# Sheet1.net
KiCad netlist of a schematic drawn in Altium Designer
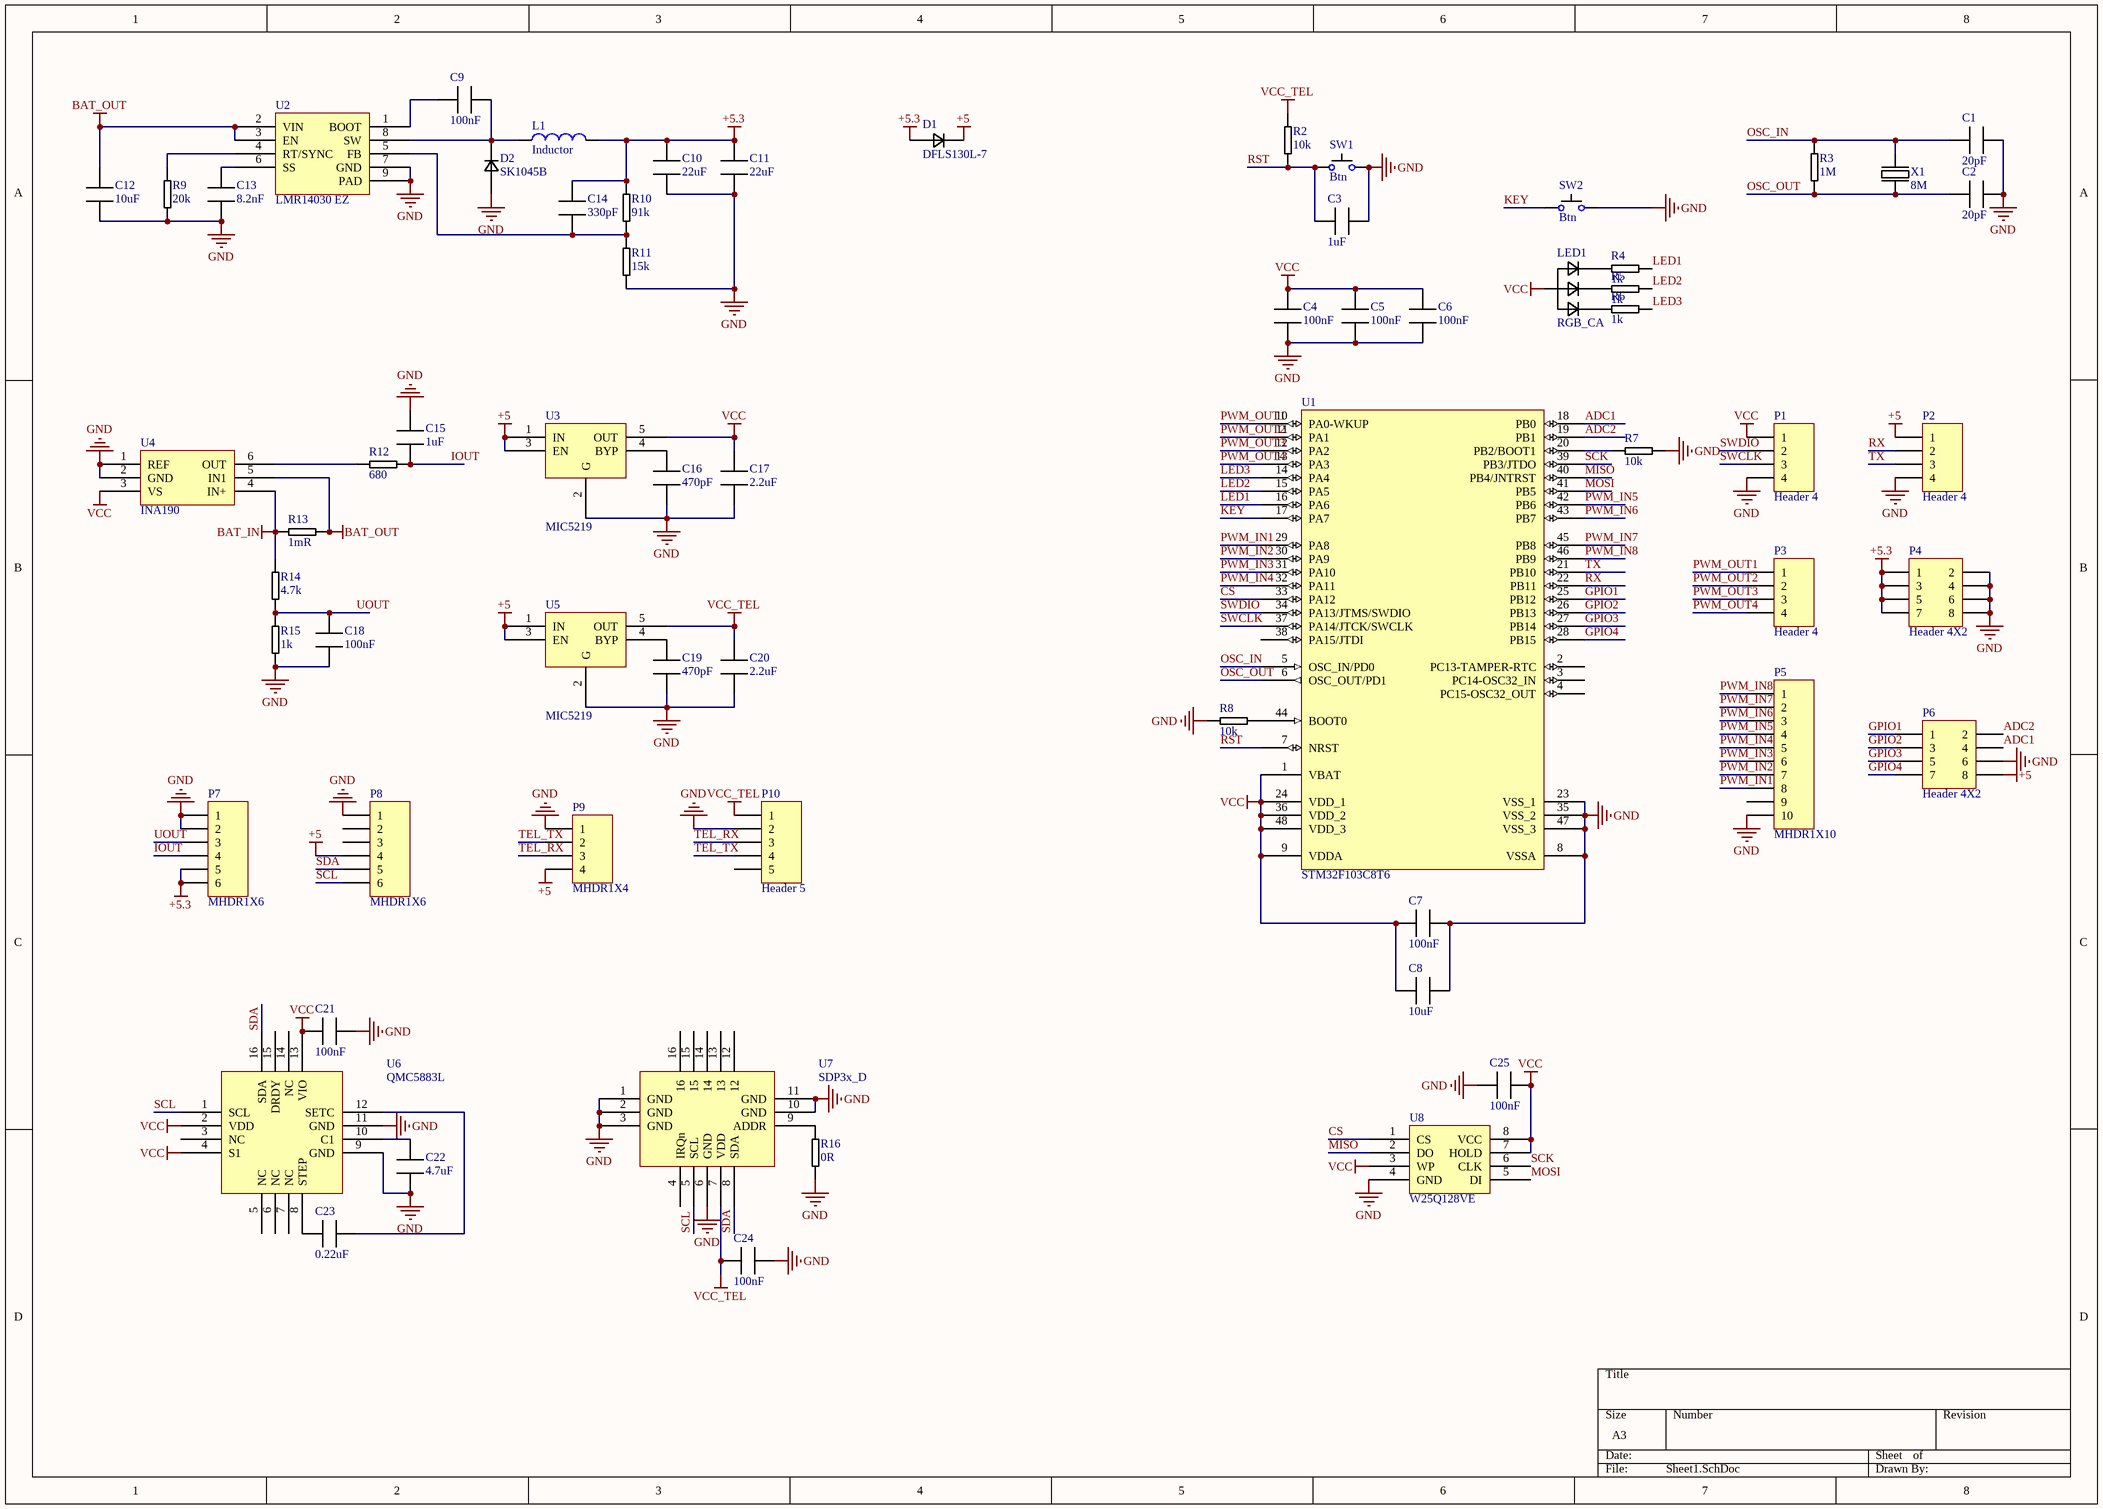
[diagram p0: Sheet1.SchDoc]

(export (version "E")
  (design (tool "Eeschema 10.0.6"))
  (components
    (comp (ref "C1") (value "20pF") (footprint "0603") (libsource (lib "LibCfrpg") (part "Cap")))
    (comp (ref "C2") (value "20pF") (footprint "0603") (libsource (lib "LibCfrpg") (part "Cap")))
    (comp (ref "C3") (value "1uF") (footprint "0603") (libsource (lib "LibCfrpg") (part "Cap")))
    (comp (ref "C4") (value "100nF") (footprint "0603") (libsource (lib "LibCfrpg") (part "Cap")))
    (comp (ref "C5") (value "100nF") (footprint "0603") (libsource (lib "LibCfrpg") (part "Cap")))
    (comp (ref "C6") (value "100nF") (footprint "0603") (libsource (lib "LibCfrpg") (part "Cap")))
    (comp (ref "C7") (value "100nF") (footprint "0603") (libsource (lib "LibCfrpg") (part "Cap")))
    (comp (ref "C8") (value "10uF") (footprint "0603") (libsource (lib "LibCfrpg") (part "Cap")))
    (comp (ref "C9") (value "100nF") (footprint "0603") (libsource (lib "LibCfrpg") (part "Cap")))
    (comp (ref "C10") (value "22uF") (footprint "0603") (libsource (lib "LibCfrpg") (part "Cap")))
    (comp (ref "C11") (value "22uF") (footprint "0603") (libsource (lib "LibCfrpg") (part "Cap")))
    (comp (ref "C12") (value "10uF") (footprint "1210") (libsource (lib "LibCfrpg") (part "Cap")))
    (comp (ref "C13") (value "8.2nF") (footprint "0603") (libsource (lib "LibCfrpg") (part "Cap")))
    (comp (ref "C14") (value "330pF") (footprint "0603") (libsource (lib "LibCfrpg") (part "Cap")))
    (comp (ref "C15") (value "1uF") (footprint "0603") (libsource (lib "LibCfrpg") (part "Cap")))
    (comp (ref "C16") (value "470pF") (footprint "0603") (libsource (lib "LibCfrpg") (part "Cap")))
    (comp (ref "C17") (value "2.2uF") (footprint "0603") (libsource (lib "LibCfrpg") (part "Cap")))
    (comp (ref "C18") (value "100nF") (footprint "0603") (libsource (lib "LibCfrpg") (part "Cap")))
    (comp (ref "C19") (value "470pF") (footprint "0603") (libsource (lib "LibCfrpg") (part "Cap")))
    (comp (ref "C20") (value "2.2uF") (footprint "0603") (libsource (lib "LibCfrpg") (part "Cap")))
    (comp (ref "C21") (value "100nF") (footprint "0603") (libsource (lib "LibCfrpg") (part "Cap")))
    (comp (ref "C22") (value "4.7uF") (footprint "0603") (libsource (lib "LibCfrpg") (part "Cap")))
    (comp (ref "C23") (value "0.22uF") (footprint "0603") (libsource (lib "LibCfrpg") (part "Cap")))
    (comp (ref "C24") (value "100nF") (footprint "0603") (libsource (lib "LibCfrpg") (part "Cap")))
    (comp (ref "C25") (value "100nF") (footprint "0603") (libsource (lib "LibCfrpg") (part "Cap")))
    (comp (ref "D1")
      (value "DFLS130L-7")
      (footprint "PowerDI123")
      (libsource (lib "LibCfrpg") (part "Diode"))
    )
    (comp (ref "D2")
      (value "SK1045B")
      (footprint "SMB (DO-214AA)")
      (libsource (lib "LibCfrpg") (part "Diode"))
    )
    (comp (ref "L1") (value "Inductor") (footprint "Ind1040") (libsource (lib "LibCfrpg") (part "Inductor")))
    (comp (ref "LED1") (value "RGB_CA") (footprint "RGB1.6*1.6") (libsource (lib "LibCfrpg") (part "RGB_CA")))
    (comp (ref "P1")
      (value "Header 4")
      (footprint "HDR1X4")
      (description "Header, 4-Pin")
      (fields (field (name "PUBLISHER") "Altium Limited"))
      (libsource (lib "Miscellaneous Connectors") (part "Header 4"))
    )
    (comp (ref "P2")
      (value "Header 4")
      (footprint "HDR1X4")
      (description "Header, 4-Pin")
      (fields (field (name "PUBLISHER") "Altium Limited"))
      (libsource (lib "Miscellaneous Connectors") (part "Header 4"))
    )
    (comp (ref "P3")
      (value "Header 4")
      (footprint "HDR1X4")
      (description "Header, 4-Pin")
      (fields (field (name "PUBLISHER") "Altium Limited"))
      (libsource (lib "Miscellaneous Connectors") (part "Header 4"))
    )
    (comp (ref "P4")
      (value "Header 4X2")
      (footprint "HDR2X4")
      (description "Header, 4-Pin, Dual row")
      (fields (field (name "PUBLISHER") "Altium Limited"))
      (libsource (lib "Miscellaneous Connectors") (part "Header 4X2"))
    )
    (comp (ref "P5")
      (value "MHDR1X10")
      (footprint "MHDR1X10")
      (description "Header, 10-Pin")
      (fields (field (name "PUBLISHER") "Altium Limited"))
      (libsource (lib "Miscellaneous Connectors") (part "MHDR1X10"))
    )
    (comp (ref "P6")
      (value "Header 4X2")
      (footprint "HDR2X4")
      (description "Header, 4-Pin, Dual row")
      (fields (field (name "PUBLISHER") "Altium Limited"))
      (libsource (lib "Miscellaneous Connectors") (part "Header 4X2"))
    )
    (comp (ref "P7")
      (value "MHDR1X6")
      (footprint "MHDR1X6")
      (description "Header, 6-Pin")
      (fields (field (name "PUBLISHER") "Altium Limited"))
      (libsource (lib "Miscellaneous Connectors") (part "MHDR1X6"))
    )
    (comp (ref "P8")
      (value "MHDR1X6")
      (footprint "MHDR1X6")
      (description "Header, 6-Pin")
      (fields (field (name "PUBLISHER") "Altium Limited"))
      (libsource (lib "Miscellaneous Connectors") (part "MHDR1X6"))
    )
    (comp (ref "P9")
      (value "MHDR1X4")
      (footprint "MHDR1X4")
      (description "Header, 4-Pin")
      (fields (field (name "PUBLISHER") "Altium Limited"))
      (libsource (lib "Miscellaneous Connectors") (part "MHDR1X4"))
    )
    (comp (ref "P10")
      (value "Header 5")
      (footprint "HDR1X5")
      (description "Header, 5-Pin")
      (fields (field (name "PUBLISHER") "Altium Limited"))
      (libsource (lib "Miscellaneous Connectors") (part "Header 5"))
    )
    (comp (ref "R2") (value "10k") (footprint "0603") (libsource (lib "LibCfrpg") (part "Res")))
    (comp (ref "R3") (value "1M") (footprint "0603") (libsource (lib "LibCfrpg") (part "Res")))
    (comp (ref "R4") (value "1k") (footprint "0603") (libsource (lib "LibCfrpg") (part "Res")))
    (comp (ref "R5") (value "1k") (footprint "0603") (libsource (lib "LibCfrpg") (part "Res")))
    (comp (ref "R6") (value "1k") (footprint "0603") (libsource (lib "LibCfrpg") (part "Res")))
    (comp (ref "R7") (value "10k") (footprint "0603") (libsource (lib "LibCfrpg") (part "Res")))
    (comp (ref "R8") (value "10k") (footprint "0603") (libsource (lib "LibCfrpg") (part "Res")))
    (comp (ref "R9") (value "20k") (footprint "0603") (libsource (lib "LibCfrpg") (part "Res")))
    (comp (ref "R10") (value "91k") (footprint "0603") (libsource (lib "LibCfrpg") (part "Res")))
    (comp (ref "R11") (value "15k") (footprint "0603") (libsource (lib "LibCfrpg") (part "Res")))
    (comp (ref "R12") (value "680") (footprint "0603") (libsource (lib "LibCfrpg") (part "Res")))
    (comp (ref "R13") (value "1mR") (footprint "2512") (libsource (lib "LibCfrpg") (part "Res")))
    (comp (ref "R14") (value "4.7k") (footprint "0603") (libsource (lib "LibCfrpg") (part "Res")))
    (comp (ref "R15") (value "1k") (footprint "0603") (libsource (lib "LibCfrpg") (part "Res")))
    (comp (ref "R16") (value "0R") (footprint "0603") (libsource (lib "LibCfrpg") (part "Res")))
    (comp (ref "SW1") (value "Btn") (footprint "BTN_B3U_B") (libsource (lib "LibCfrpg") (part "Btn")))
    (comp (ref "SW2") (value "Btn") (footprint "BTN_B3U_B") (libsource (lib "LibCfrpg") (part "Btn")))
    (comp (ref "U1")
      (value "STM32F103C8T6")
      (footprint "LQFP48_N")
      (description "STM32 ARM-based 32-bit MCU with 64 Kbytes Flash, 48-pin LQFP, Industrial Temperature")
      (fields (field (name "PUBLISHER") "Altium Limited"))
      (libsource (lib "ST Microcontroller 32-Bit STM32") (part "STM32F103C8T6"))
    )
    (comp (ref "U2")
      (value "LMR14030 EZ")
      (footprint "SOP8-Pad")
      (libsource (lib "LibCfrpg") (part "LMR14030 EZ"))
    )
    (comp (ref "U3") (value "MIC5219") (footprint "SOT23-5") (libsource (lib "LibCfrpg") (part "MIC5219")))
    (comp (ref "U4") (value "INA190") (footprint "SC70") (libsource (lib "LibCfrpg") (part "INA190")))
    (comp (ref "U5") (value "MIC5219") (footprint "SOT23-5") (libsource (lib "LibCfrpg") (part "MIC5219")))
    (comp (ref "U6") (value "QMC5883L") (footprint "QMC5883") (libsource (lib "LibCfrpg") (part "QMC5883L")))
    (comp (ref "U7") (value "SDP3x_D") (footprint "SDP3x") (libsource (lib "LibCfrpg") (part "SDP3x_D")))
    (comp (ref "U8")
      (value "W25Q128VE")
      (footprint "WSON8-8x6mm")
      (libsource (lib "LibCfrpg") (part "W25QxxxVE/A"))
    )
    (comp (ref "X1") (value "8M") (footprint "XTAL-3225-4") (libsource (lib "LibCfrpg") (part "XTAL")))
  )
  (nets
    (net (code "1") (name "+5") (class "Default")
      (node (ref "D1") (pin "2") (pintype "passive"))
      (node (ref "P2") (pin "1") (pinfunction "1_1") (pintype "passive"))
      (node (ref "P6") (pin "8") (pinfunction "8_8") (pintype "passive"))
      (node (ref "P8") (pin "4") (pinfunction "4_4") (pintype "passive"))
      (node (ref "P9") (pin "4") (pinfunction "4_4") (pintype "passive"))
      (node (ref "U3") (pin "1") (pinfunction "IN_1") (pintype "passive"))
      (node (ref "U3") (pin "3") (pinfunction "EN_3") (pintype "passive"))
      (node (ref "U5") (pin "1") (pinfunction "IN_1") (pintype "passive"))
      (node (ref "U5") (pin "3") (pinfunction "EN_3") (pintype "passive"))
    )
    (net (code "2") (name "+5.3") (class "Default")
      (node (ref "C10") (pin "2") (pintype "passive"))
      (node (ref "C11") (pin "2") (pintype "passive"))
      (node (ref "C14") (pin "2") (pintype "passive"))
      (node (ref "D1") (pin "1") (pintype "passive"))
      (node (ref "L1") (pin "2") (pinfunction "2_2") (pintype "passive"))
      (node (ref "P4") (pin "1") (pinfunction "1_1") (pintype "passive"))
      (node (ref "P4") (pin "3") (pinfunction "3_3") (pintype "passive"))
      (node (ref "P4") (pin "5") (pinfunction "5_5") (pintype "passive"))
      (node (ref "P4") (pin "7") (pinfunction "7_7") (pintype "passive"))
      (node (ref "P7") (pin "5") (pinfunction "5_5") (pintype "passive"))
      (node (ref "P7") (pin "6") (pinfunction "6_6") (pintype "passive"))
      (node (ref "R10") (pin "2") (pintype "passive"))
    )
    (net (code "3") (name "/ADC1") (class "Default")
      (node (ref "P6") (pin "4") (pinfunction "4_4") (pintype "passive"))
      (node (ref "U1") (pin "18") (pinfunction "PB0_18") (pintype "bidirectional"))
    )
    (net (code "4") (name "/ADC2") (class "Default")
      (node (ref "P6") (pin "2") (pinfunction "2_2") (pintype "passive"))
      (node (ref "U1") (pin "19") (pinfunction "PB1_19") (pintype "bidirectional"))
    )
    (net (code "5") (name "/CS") (class "Default")
      (node (ref "U1") (pin "33") (pinfunction "PA12_33") (pintype "bidirectional"))
      (node (ref "U8") (pin "1") (pinfunction "CS_1") (pintype "passive"))
    )
    (net (code "6") (name "/GPIO1") (class "Default")
      (node (ref "P6") (pin "1") (pinfunction "1_1") (pintype "passive"))
      (node (ref "U1") (pin "25") (pinfunction "PB12_25") (pintype "bidirectional"))
    )
    (net (code "7") (name "/GPIO2") (class "Default")
      (node (ref "P6") (pin "3") (pinfunction "3_3") (pintype "passive"))
      (node (ref "U1") (pin "26") (pinfunction "PB13_26") (pintype "bidirectional"))
    )
    (net (code "8") (name "/GPIO3") (class "Default")
      (node (ref "P6") (pin "5") (pinfunction "5_5") (pintype "passive"))
      (node (ref "U1") (pin "27") (pinfunction "PB14_27") (pintype "bidirectional"))
    )
    (net (code "9") (name "/GPIO4") (class "Default")
      (node (ref "P6") (pin "7") (pinfunction "7_7") (pintype "passive"))
      (node (ref "U1") (pin "28") (pinfunction "PB15_28") (pintype "bidirectional"))
    )
    (net (code "10") (name "/IOUT") (class "Default")
      (node (ref "C15") (pin "1") (pintype "passive"))
      (node (ref "P7") (pin "4") (pinfunction "4_4") (pintype "passive"))
      (node (ref "R12") (pin "2") (pintype "passive"))
    )
    (net (code "11") (name "/KEY") (class "Default")
      (node (ref "SW2") (pin "1") (pintype "passive"))
      (node (ref "U1") (pin "17") (pinfunction "PA7_17") (pintype "bidirectional"))
    )
    (net (code "12") (name "/LED1") (class "Default")
      (node (ref "R4") (pin "2") (pintype "passive"))
      (node (ref "U1") (pin "16") (pinfunction "PA6_16") (pintype "bidirectional"))
    )
    (net (code "13") (name "/LED2") (class "Default")
      (node (ref "R5") (pin "2") (pintype "passive"))
      (node (ref "U1") (pin "15") (pinfunction "PA5_15") (pintype "bidirectional"))
    )
    (net (code "14") (name "/LED3") (class "Default")
      (node (ref "R6") (pin "2") (pintype "passive"))
      (node (ref "U1") (pin "14") (pinfunction "PA4_14") (pintype "bidirectional"))
    )
    (net (code "15") (name "/MISO") (class "Default")
      (node (ref "U1") (pin "40") (pinfunction "PB4/JNTRST_40") (pintype "bidirectional"))
      (node (ref "U8") (pin "2") (pinfunction "DO_2") (pintype "passive"))
    )
    (net (code "16") (name "/MOSI") (class "Default")
      (node (ref "U1") (pin "41") (pinfunction "PB5_41") (pintype "bidirectional"))
      (node (ref "U8") (pin "5") (pinfunction "DI_5") (pintype "passive"))
    )
    (net (code "17") (name "/OSC_IN") (class "Default")
      (node (ref "C1") (pin "1") (pintype "passive"))
      (node (ref "R3") (pin "2") (pintype "passive"))
      (node (ref "U1") (pin "5") (pinfunction "OSC_IN/PD0_5") (pintype "input"))
      (node (ref "X1") (pin "2") (pintype "passive"))
    )
    (net (code "18") (name "/OSC_OUT") (class "Default")
      (node (ref "C2") (pin "1") (pintype "passive"))
      (node (ref "R3") (pin "1") (pintype "passive"))
      (node (ref "U1") (pin "6") (pinfunction "OSC_OUT/PD1_6") (pintype "output"))
      (node (ref "X1") (pin "1") (pintype "passive"))
    )
    (net (code "19") (name "/PWM_IN1") (class "Default")
      (node (ref "P5") (pin "8") (pinfunction "8_8") (pintype "passive"))
      (node (ref "U1") (pin "29") (pinfunction "PA8_29") (pintype "bidirectional"))
    )
    (net (code "20") (name "/PWM_IN2") (class "Default")
      (node (ref "P5") (pin "7") (pinfunction "7_7") (pintype "passive"))
      (node (ref "U1") (pin "30") (pinfunction "PA9_30") (pintype "bidirectional"))
    )
    (net (code "21") (name "/PWM_IN3") (class "Default")
      (node (ref "P5") (pin "6") (pinfunction "6_6") (pintype "passive"))
      (node (ref "U1") (pin "31") (pinfunction "PA10_31") (pintype "bidirectional"))
    )
    (net (code "22") (name "/PWM_IN4") (class "Default")
      (node (ref "P5") (pin "5") (pinfunction "5_5") (pintype "passive"))
      (node (ref "U1") (pin "32") (pinfunction "PA11_32") (pintype "bidirectional"))
    )
    (net (code "23") (name "/PWM_IN5") (class "Default")
      (node (ref "P5") (pin "4") (pinfunction "4_4") (pintype "passive"))
      (node (ref "U1") (pin "42") (pinfunction "PB6_42") (pintype "bidirectional"))
    )
    (net (code "24") (name "/PWM_IN6") (class "Default")
      (node (ref "P5") (pin "3") (pinfunction "3_3") (pintype "passive"))
      (node (ref "U1") (pin "43") (pinfunction "PB7_43") (pintype "bidirectional"))
    )
    (net (code "25") (name "/PWM_IN7") (class "Default")
      (node (ref "P5") (pin "2") (pinfunction "2_2") (pintype "passive"))
      (node (ref "U1") (pin "45") (pinfunction "PB8_45") (pintype "bidirectional"))
    )
    (net (code "26") (name "/PWM_IN8") (class "Default")
      (node (ref "P5") (pin "1") (pinfunction "1_1") (pintype "passive"))
      (node (ref "U1") (pin "46") (pinfunction "PB9_46") (pintype "bidirectional"))
    )
    (net (code "27") (name "/PWM_OUT1") (class "Default")
      (node (ref "P3") (pin "1") (pinfunction "1_1") (pintype "passive"))
      (node (ref "U1") (pin "10") (pinfunction "PA0-WKUP_10") (pintype "bidirectional"))
    )
    (net (code "28") (name "/PWM_OUT2") (class "Default")
      (node (ref "P3") (pin "2") (pinfunction "2_2") (pintype "passive"))
      (node (ref "U1") (pin "11") (pinfunction "PA1_11") (pintype "bidirectional"))
    )
    (net (code "29") (name "/PWM_OUT3") (class "Default")
      (node (ref "P3") (pin "3") (pinfunction "3_3") (pintype "passive"))
      (node (ref "U1") (pin "12") (pinfunction "PA2_12") (pintype "bidirectional"))
    )
    (net (code "30") (name "/PWM_OUT4") (class "Default")
      (node (ref "P3") (pin "4") (pinfunction "4_4") (pintype "passive"))
      (node (ref "U1") (pin "13") (pinfunction "PA3_13") (pintype "bidirectional"))
    )
    (net (code "31") (name "/RST") (class "Default")
      (node (ref "C3") (pin "1") (pintype "passive"))
      (node (ref "R2") (pin "1") (pintype "passive"))
      (node (ref "SW1") (pin "1") (pintype "passive"))
      (node (ref "U1") (pin "7") (pinfunction "NRST_7") (pintype "bidirectional"))
    )
    (net (code "32") (name "/RX") (class "Default")
      (node (ref "P2") (pin "2") (pinfunction "2_2") (pintype "passive"))
      (node (ref "U1") (pin "22") (pinfunction "PB11_22") (pintype "bidirectional"))
    )
    (net (code "33") (name "/SCK") (class "Default")
      (node (ref "U1") (pin "39") (pinfunction "PB3/JTDO_39") (pintype "bidirectional"))
      (node (ref "U8") (pin "6") (pinfunction "CLK_6") (pintype "passive"))
    )
    (net (code "34") (name "/SCL") (class "Default")
      (node (ref "P8") (pin "6") (pinfunction "6_6") (pintype "passive"))
      (node (ref "U6") (pin "1") (pinfunction "SCL_1") (pintype "passive"))
      (node (ref "U7") (pin "5") (pinfunction "SCL_5") (pintype "passive"))
    )
    (net (code "35") (name "/SDA") (class "Default")
      (node (ref "P8") (pin "5") (pinfunction "5_5") (pintype "passive"))
      (node (ref "U6") (pin "16") (pinfunction "SDA_16") (pintype "passive"))
      (node (ref "U7") (pin "8") (pinfunction "SDA_8") (pintype "passive"))
    )
    (net (code "36") (name "/SWCLK") (class "Default")
      (node (ref "P1") (pin "3") (pinfunction "3_3") (pintype "passive"))
      (node (ref "U1") (pin "37") (pinfunction "PA14/JTCK/SWCLK_37") (pintype "bidirectional"))
    )
    (net (code "37") (name "/SWDIO") (class "Default")
      (node (ref "P1") (pin "2") (pinfunction "2_2") (pintype "passive"))
      (node (ref "U1") (pin "34") (pinfunction "PA13/JTMS/SWDIO_34") (pintype "bidirectional"))
    )
    (net (code "38") (name "/TEL_RX") (class "Default")
      (node (ref "P10") (pin "3") (pinfunction "3_3") (pintype "passive"))
      (node (ref "P9") (pin "3") (pinfunction "3_3") (pintype "passive"))
    )
    (net (code "39") (name "/TEL_TX") (class "Default")
      (node (ref "P10") (pin "4") (pinfunction "4_4") (pintype "passive"))
      (node (ref "P9") (pin "2") (pinfunction "2_2") (pintype "passive"))
    )
    (net (code "40") (name "/TX") (class "Default")
      (node (ref "P2") (pin "3") (pinfunction "3_3") (pintype "passive"))
      (node (ref "U1") (pin "21") (pinfunction "PB10_21") (pintype "bidirectional"))
    )
    (net (code "41") (name "/UOUT") (class "Default")
      (node (ref "C18") (pin "2") (pintype "passive"))
      (node (ref "P7") (pin "3") (pinfunction "3_3") (pintype "passive"))
      (node (ref "R14") (pin "1") (pintype "passive"))
      (node (ref "R15") (pin "2") (pintype "passive"))
    )
    (net (code "42") (name "BAT_IN") (class "Default")
      (node (ref "R13") (pin "1") (pintype "passive"))
      (node (ref "R14") (pin "2") (pintype "passive"))
      (node (ref "U4") (pin "4") (pinfunction "IN+_4") (pintype "passive"))
    )
    (net (code "43") (name "BAT_OUT") (class "Default")
      (node (ref "C12") (pin "2") (pintype "passive"))
      (node (ref "R13") (pin "2") (pintype "passive"))
      (node (ref "U2") (pin "2") (pinfunction "VIN_2") (pintype "passive"))
      (node (ref "U2") (pin "3") (pinfunction "EN_3") (pintype "passive"))
      (node (ref "U4") (pin "5") (pinfunction "IN1_5") (pintype "passive"))
    )
    (net (code "44") (name "GND") (class "Default")
      (node (ref "C1") (pin "2") (pintype "passive"))
      (node (ref "C10") (pin "1") (pintype "passive"))
      (node (ref "C11") (pin "1") (pintype "passive"))
      (node (ref "C12") (pin "1") (pintype "passive"))
      (node (ref "C13") (pin "1") (pintype "passive"))
      (node (ref "C15") (pin "2") (pintype "passive"))
      (node (ref "C16") (pin "1") (pintype "passive"))
      (node (ref "C17") (pin "1") (pintype "passive"))
      (node (ref "C18") (pin "1") (pintype "passive"))
      (node (ref "C19") (pin "1") (pintype "passive"))
      (node (ref "C2") (pin "2") (pintype "passive"))
      (node (ref "C20") (pin "1") (pintype "passive"))
      (node (ref "C21") (pin "2") (pintype "passive"))
      (node (ref "C22") (pin "1") (pintype "passive"))
      (node (ref "C24") (pin "2") (pintype "passive"))
      (node (ref "C25") (pin "1") (pintype "passive"))
      (node (ref "C3") (pin "2") (pintype "passive"))
      (node (ref "C4") (pin "1") (pintype "passive"))
      (node (ref "C5") (pin "1") (pintype "passive"))
      (node (ref "C6") (pin "1") (pintype "passive"))
      (node (ref "C7") (pin "2") (pintype "passive"))
      (node (ref "C8") (pin "2") (pintype "passive"))
      (node (ref "D2") (pin "1") (pintype "passive"))
      (node (ref "P1") (pin "4") (pinfunction "4_4") (pintype "passive"))
      (node (ref "P10") (pin "2") (pinfunction "2_2") (pintype "passive"))
      (node (ref "P2") (pin "4") (pinfunction "4_4") (pintype "passive"))
      (node (ref "P4") (pin "2") (pinfunction "2_2") (pintype "passive"))
      (node (ref "P4") (pin "4") (pinfunction "4_4") (pintype "passive"))
      (node (ref "P4") (pin "6") (pinfunction "6_6") (pintype "passive"))
      (node (ref "P4") (pin "8") (pinfunction "8_8") (pintype "passive"))
      (node (ref "P5") (pin "10") (pinfunction "10_10") (pintype "passive"))
      (node (ref "P6") (pin "6") (pinfunction "6_6") (pintype "passive"))
      (node (ref "P7") (pin "1") (pinfunction "1_1") (pintype "passive"))
      (node (ref "P7") (pin "2") (pinfunction "2_2") (pintype "passive"))
      (node (ref "P8") (pin "1") (pinfunction "1_1") (pintype "passive"))
      (node (ref "P9") (pin "1") (pinfunction "1_1") (pintype "passive"))
      (node (ref "R11") (pin "1") (pintype "passive"))
      (node (ref "R15") (pin "1") (pintype "passive"))
      (node (ref "R16") (pin "1") (pintype "passive"))
      (node (ref "R7") (pin "2") (pintype "passive"))
      (node (ref "R8") (pin "1") (pintype "passive"))
      (node (ref "R9") (pin "1") (pintype "passive"))
      (node (ref "SW1") (pin "2") (pintype "passive"))
      (node (ref "SW2") (pin "2") (pintype "passive"))
      (node (ref "U1") (pin "23") (pinfunction "VSS_1_23") (pintype "power_in"))
      (node (ref "U1") (pin "35") (pinfunction "VSS_2_35") (pintype "power_in"))
      (node (ref "U1") (pin "47") (pinfunction "VSS_3_47") (pintype "power_in"))
      (node (ref "U1") (pin "8") (pinfunction "VSSA_8") (pintype "power_in"))
      (node (ref "U2") (pin "7") (pinfunction "GND_7") (pintype "passive"))
      (node (ref "U2") (pin "9") (pinfunction "PAD_9") (pintype "passive"))
      (node (ref "U3") (pin "2") (pinfunction "G_2") (pintype "passive"))
      (node (ref "U4") (pin "1") (pinfunction "REF_1") (pintype "passive"))
      (node (ref "U4") (pin "2") (pinfunction "GND_2") (pintype "passive"))
      (node (ref "U5") (pin "2") (pinfunction "G_2") (pintype "passive"))
      (node (ref "U6") (pin "11") (pinfunction "GND_11") (pintype "passive"))
      (node (ref "U6") (pin "9") (pinfunction "GND_9") (pintype "passive"))
      (node (ref "U7") (pin "1") (pinfunction "GND_1") (pintype "passive"))
      (node (ref "U7") (pin "10") (pinfunction "GND_10") (pintype "passive"))
      (node (ref "U7") (pin "11") (pinfunction "GND_11") (pintype "passive"))
      (node (ref "U7") (pin "2") (pinfunction "GND_2") (pintype "passive"))
      (node (ref "U7") (pin "3") (pinfunction "GND_3") (pintype "passive"))
      (node (ref "U7") (pin "6") (pinfunction "GND_6") (pintype "passive"))
      (node (ref "U8") (pin "4") (pinfunction "GND_4") (pintype "passive"))
    )
    (net (code "45") (name "Net-(LED1-Pad1)") (class "Default")
      (node (ref "LED1") (pin "1") (pintype "passive"))
      (node (ref "R4") (pin "1") (pintype "passive"))
    )
    (net (code "46") (name "Net-(LED1-Pad2)") (class "Default")
      (node (ref "LED1") (pin "2") (pintype "passive"))
      (node (ref "R5") (pin "1") (pintype "passive"))
    )
    (net (code "47") (name "Net-(LED1-Pad3)") (class "Default")
      (node (ref "LED1") (pin "3") (pintype "passive"))
      (node (ref "R6") (pin "1") (pintype "passive"))
    )
    (net (code "48") (name "Net-(U1-BOOT0)") (class "Default")
      (node (ref "R8") (pin "2") (pintype "passive"))
      (node (ref "U1") (pin "44") (pinfunction "BOOT0_44") (pintype "input"))
    )
    (net (code "49") (name "Net-(U1-PB2{slash}BOOT1)") (class "Default")
      (node (ref "R7") (pin "1") (pintype "passive"))
      (node (ref "U1") (pin "20") (pinfunction "PB2/BOOT1_20") (pintype "bidirectional"))
    )
    (net (code "50") (name "Net-(U2-BOOT)") (class "Default")
      (node (ref "C9") (pin "1") (pintype "passive"))
      (node (ref "U2") (pin "1") (pinfunction "BOOT_1") (pintype "passive"))
    )
    (net (code "51") (name "Net-(U2-FB)") (class "Default")
      (node (ref "C14") (pin "1") (pintype "passive"))
      (node (ref "R10") (pin "1") (pintype "passive"))
      (node (ref "R11") (pin "2") (pintype "passive"))
      (node (ref "U2") (pin "5") (pinfunction "FB_5") (pintype "passive"))
    )
    (net (code "52") (name "Net-(U2-RT{slash}SYNC)") (class "Default")
      (node (ref "R9") (pin "2") (pintype "passive"))
      (node (ref "U2") (pin "4") (pinfunction "RT/SYNC_4") (pintype "passive"))
    )
    (net (code "53") (name "Net-(U2-SS)") (class "Default")
      (node (ref "C13") (pin "2") (pintype "passive"))
      (node (ref "U2") (pin "6") (pinfunction "SS_6") (pintype "passive"))
    )
    (net (code "54") (name "Net-(U2-SW)") (class "Default")
      (node (ref "C9") (pin "2") (pintype "passive"))
      (node (ref "D2") (pin "2") (pintype "passive"))
      (node (ref "L1") (pin "1") (pinfunction "1_1") (pintype "passive"))
      (node (ref "U2") (pin "8") (pinfunction "SW_8") (pintype "passive"))
    )
    (net (code "55") (name "Net-(U3-BYP)") (class "Default")
      (node (ref "C16") (pin "2") (pintype "passive"))
      (node (ref "U3") (pin "4") (pinfunction "BYP_4") (pintype "passive"))
    )
    (net (code "56") (name "Net-(U4-OUT)") (class "Default")
      (node (ref "R12") (pin "1") (pintype "passive"))
      (node (ref "U4") (pin "6") (pinfunction "OUT_6") (pintype "passive"))
    )
    (net (code "57") (name "Net-(U5-BYP)") (class "Default")
      (node (ref "C19") (pin "2") (pintype "passive"))
      (node (ref "U5") (pin "4") (pinfunction "BYP_4") (pintype "passive"))
    )
    (net (code "58") (name "Net-(U6-C1)") (class "Default")
      (node (ref "C22") (pin "2") (pintype "passive"))
      (node (ref "U6") (pin "10") (pinfunction "C1_10") (pintype "passive"))
    )
    (net (code "59") (name "Net-(U6-SETC)") (class "Default")
      (node (ref "C23") (pin "2") (pintype "passive"))
      (node (ref "U6") (pin "12") (pinfunction "SETC_12") (pintype "passive"))
    )
    (net (code "60") (name "Net-(U6-STEP)") (class "Default")
      (node (ref "C23") (pin "1") (pintype "passive"))
      (node (ref "U6") (pin "8") (pinfunction "STEP_8") (pintype "passive"))
    )
    (net (code "61") (name "Net-(U7-ADDR)") (class "Default")
      (node (ref "R16") (pin "2") (pintype "passive"))
      (node (ref "U7") (pin "9") (pinfunction "ADDR_9") (pintype "passive"))
    )
    (net (code "62") (name "VCC") (class "Default")
      (node (ref "C17") (pin "2") (pintype "passive"))
      (node (ref "C21") (pin "1") (pintype "passive"))
      (node (ref "C25") (pin "2") (pintype "passive"))
      (node (ref "C4") (pin "2") (pintype "passive"))
      (node (ref "C5") (pin "2") (pintype "passive"))
      (node (ref "C6") (pin "2") (pintype "passive"))
      (node (ref "C7") (pin "1") (pintype "passive"))
      (node (ref "C8") (pin "1") (pintype "passive"))
      (node (ref "LED1") (pin "4") (pintype "passive"))
      (node (ref "P1") (pin "1") (pinfunction "1_1") (pintype "passive"))
      (node (ref "U1") (pin "1") (pinfunction "VBAT_1") (pintype "power_in"))
      (node (ref "U1") (pin "24") (pinfunction "VDD_1_24") (pintype "power_in"))
      (node (ref "U1") (pin "36") (pinfunction "VDD_2_36") (pintype "power_in"))
      (node (ref "U1") (pin "48") (pinfunction "VDD_3_48") (pintype "power_in"))
      (node (ref "U1") (pin "9") (pinfunction "VDDA_9") (pintype "power_in"))
      (node (ref "U3") (pin "5") (pinfunction "OUT_5") (pintype "passive"))
      (node (ref "U4") (pin "3") (pinfunction "VS_3") (pintype "passive"))
      (node (ref "U6") (pin "13") (pinfunction "VIO_13") (pintype "passive"))
      (node (ref "U6") (pin "2") (pinfunction "VDD_2") (pintype "passive"))
      (node (ref "U6") (pin "4") (pinfunction "S1_4") (pintype "passive"))
      (node (ref "U8") (pin "3") (pinfunction "WP_3") (pintype "passive"))
      (node (ref "U8") (pin "7") (pinfunction "HOLD_7") (pintype "passive"))
      (node (ref "U8") (pin "8") (pinfunction "VCC_8") (pintype "passive"))
    )
    (net (code "63") (name "VCC_TEL") (class "Default")
      (node (ref "C20") (pin "2") (pintype "passive"))
      (node (ref "C24") (pin "1") (pintype "passive"))
      (node (ref "P10") (pin "1") (pinfunction "1_1") (pintype "passive"))
      (node (ref "R2") (pin "2") (pintype "passive"))
      (node (ref "U5") (pin "5") (pinfunction "OUT_5") (pintype "passive"))
      (node (ref "U7") (pin "7") (pinfunction "VDD_7") (pintype "passive"))
    )
    (net (code "64") (name "unconnected-(P5-Pad9)") (class "Default")
      (node (ref "P5") (pin "9") (pinfunction "9_9") (pintype "passive"))
    )
    (net (code "65") (name "unconnected-(P8-Pad2)") (class "Default")
      (node (ref "P8") (pin "2") (pinfunction "2_2") (pintype "passive"))
    )
    (net (code "66") (name "unconnected-(P8-Pad3)") (class "Default")
      (node (ref "P8") (pin "3") (pinfunction "3_3") (pintype "passive"))
    )
    (net (code "67") (name "unconnected-(P10-Pad5)") (class "Default")
      (node (ref "P10") (pin "5") (pinfunction "5_5") (pintype "passive"))
    )
    (net (code "68") (name "unconnected-(U1-PA15{slash}JTDI-Pad38)") (class "Default")
      (node (ref "U1") (pin "38") (pinfunction "PA15/JTDI_38") (pintype "bidirectional"))
    )
    (net (code "69") (name "unconnected-(U1-PC13-TAMPER-RTC-Pad2)") (class "Default")
      (node (ref "U1") (pin "2") (pinfunction "PC13-TAMPER-RTC_2") (pintype "bidirectional"))
    )
    (net (code "70") (name "unconnected-(U1-PC14-OSC32_IN-Pad3)") (class "Default")
      (node (ref "U1") (pin "3") (pinfunction "PC14-OSC32_IN_3") (pintype "bidirectional"))
    )
    (net (code "71") (name "unconnected-(U1-PC15-OSC32_OUT-Pad4)") (class "Default")
      (node (ref "U1") (pin "4") (pinfunction "PC15-OSC32_OUT_4") (pintype "bidirectional"))
    )
    (net (code "72") (name "unconnected-(U6-DRDY-Pad15)") (class "Default")
      (node (ref "U6") (pin "15") (pinfunction "DRDY_15") (pintype "passive"))
    )
    (net (code "73") (name "unconnected-(U6-NC-Pad3)") (class "Default")
      (node (ref "U6") (pin "3") (pinfunction "NC_3") (pintype "passive"))
    )
    (net (code "74") (name "unconnected-(U6-NC-Pad5)") (class "Default")
      (node (ref "U6") (pin "5") (pinfunction "NC_5") (pintype "passive"))
    )
    (net (code "75") (name "unconnected-(U6-NC-Pad6)") (class "Default")
      (node (ref "U6") (pin "6") (pinfunction "NC_6") (pintype "passive"))
    )
    (net (code "76") (name "unconnected-(U6-NC-Pad7)") (class "Default")
      (node (ref "U6") (pin "7") (pinfunction "NC_7") (pintype "passive"))
    )
    (net (code "77") (name "unconnected-(U6-NC-Pad14)") (class "Default")
      (node (ref "U6") (pin "14") (pinfunction "NC_14") (pintype "passive"))
    )
    (net (code "78") (name "unconnected-(U7-IRQn-Pad4)") (class "Default")
      (node (ref "U7") (pin "4") (pinfunction "IRQn_4") (pintype "passive"))
    )
    (net (code "79") (name "unconnected-(U7-Pad12)") (class "Default")
      (node (ref "U7") (pin "12") (pinfunction "12_12") (pintype "passive"))
    )
    (net (code "80") (name "unconnected-(U7-Pad13)") (class "Default")
      (node (ref "U7") (pin "13") (pinfunction "13_13") (pintype "passive"))
    )
    (net (code "81") (name "unconnected-(U7-Pad14)") (class "Default")
      (node (ref "U7") (pin "14") (pinfunction "14_14") (pintype "passive"))
    )
    (net (code "82") (name "unconnected-(U7-Pad15)") (class "Default")
      (node (ref "U7") (pin "15") (pinfunction "15_15") (pintype "passive"))
    )
    (net (code "83") (name "unconnected-(U7-Pad16)") (class "Default")
      (node (ref "U7") (pin "16") (pinfunction "16_16") (pintype "passive"))
    )
  )
)
